# G021vrs.net
KiCad netlist of a schematic drawn in EAGLE
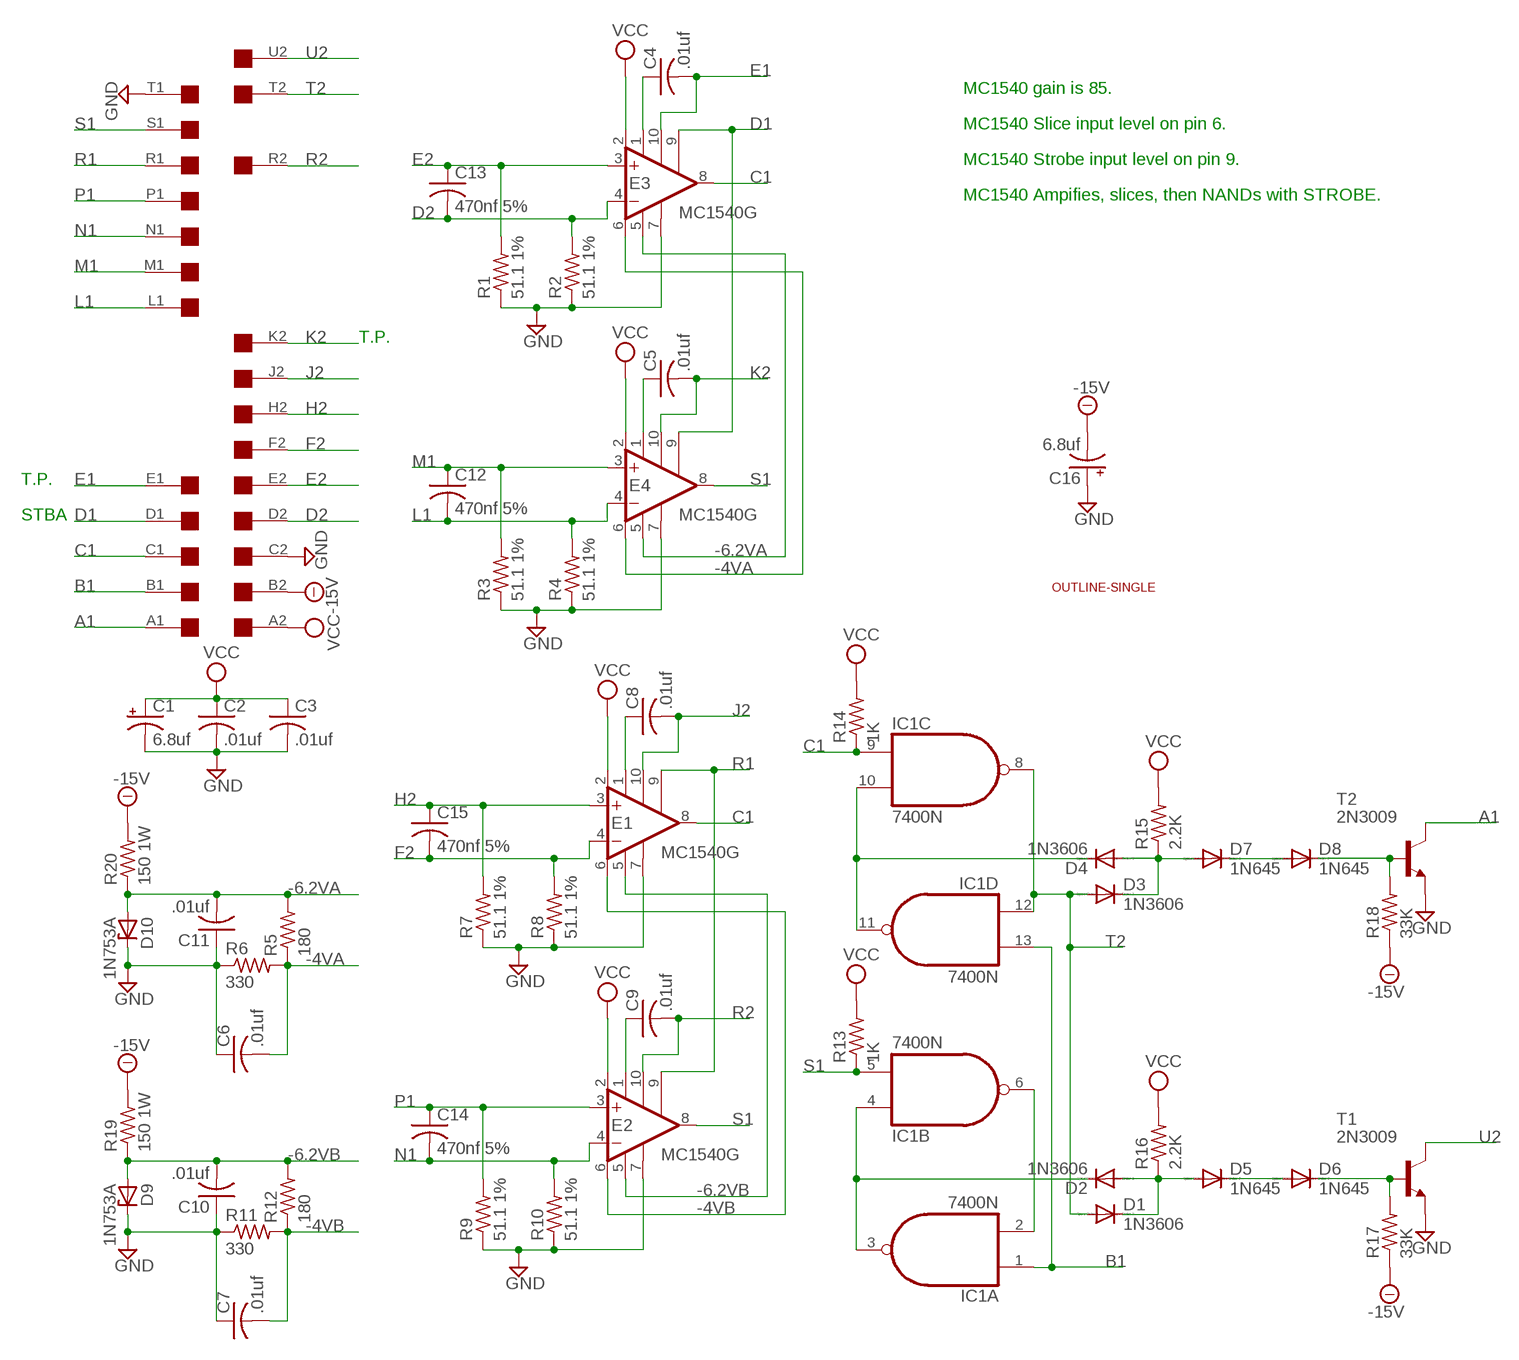
[diagram p0: schematic, sheet 1]

(export (version "E")
  (design (tool "Eeschema 10.0.6"))
  (components
    (comp (ref "C1")
      (value "6.8uf")
      (footprint "eagle-import:E15-5")
      (libsource (lib "eagle-import") (part "CPOL-USE15-5AXIAL"))
    )
    (comp (ref "C2")
      (value ".01uf")
      (footprint "eagle-import:C050-025X075")
      (libsource (lib "eagle-import") (part "C-US050-025X075"))
    )
    (comp (ref "C3")
      (value ".01uf")
      (footprint "eagle-import:C050-025X075")
      (libsource (lib "eagle-import") (part "C-US050-025X075"))
    )
    (comp (ref "C4")
      (value ".01uf")
      (footprint "eagle-import:C050-025X075")
      (libsource (lib "eagle-import") (part "C-US050-025X075"))
    )
    (comp (ref "C5")
      (value ".01uf")
      (footprint "eagle-import:C050-025X075")
      (libsource (lib "eagle-import") (part "C-US050-025X075"))
    )
    (comp (ref "C6")
      (value ".01uf")
      (footprint "eagle-import:C050-025X075")
      (libsource (lib "eagle-import") (part "C-US050-025X075"))
    )
    (comp (ref "C7")
      (value ".01uf")
      (footprint "eagle-import:C050-025X075")
      (libsource (lib "eagle-import") (part "C-US050-025X075"))
    )
    (comp (ref "C8")
      (value ".01uf")
      (footprint "eagle-import:C050-025X075")
      (libsource (lib "eagle-import") (part "C-US050-025X075"))
    )
    (comp (ref "C9")
      (value ".01uf")
      (footprint "eagle-import:C050-025X075")
      (libsource (lib "eagle-import") (part "C-US050-025X075"))
    )
    (comp (ref "C10")
      (value ".01uf")
      (footprint "eagle-import:C050-025X075")
      (libsource (lib "eagle-import") (part "C-US050-025X075"))
    )
    (comp (ref "C11")
      (value ".01uf")
      (footprint "eagle-import:C050-025X075")
      (libsource (lib "eagle-import") (part "C-US050-025X075"))
    )
    (comp (ref "C12")
      (value "470nf 5%")
      (footprint "eagle-import:C050-025X075")
      (libsource (lib "eagle-import") (part "C-US050-025X075"))
    )
    (comp (ref "C13")
      (value "470nf 5%")
      (footprint "eagle-import:C050-025X075")
      (libsource (lib "eagle-import") (part "C-US050-025X075"))
    )
    (comp (ref "C14")
      (value "470nf 5%")
      (footprint "eagle-import:C050-025X075")
      (libsource (lib "eagle-import") (part "C-US050-025X075"))
    )
    (comp (ref "C15")
      (value "470nf 5%")
      (footprint "eagle-import:C050-025X075")
      (libsource (lib "eagle-import") (part "C-US050-025X075"))
    )
    (comp (ref "C16")
      (value "6.8uf")
      (footprint "eagle-import:E15-5")
      (libsource (lib "eagle-import") (part "CPOL-USE15-5AXIAL"))
    )
    (comp (ref "D1")
      (value "1N3606")
      (footprint "eagle-import:DO35-10")
      (libsource (lib "eagle-import") (part "1N4148DO35-10"))
    )
    (comp (ref "D2")
      (value "1N3606")
      (footprint "eagle-import:DO35-10")
      (libsource (lib "eagle-import") (part "1N4148DO35-10"))
    )
    (comp (ref "D3")
      (value "1N3606")
      (footprint "eagle-import:DO35-10")
      (libsource (lib "eagle-import") (part "1N4148DO35-10"))
    )
    (comp (ref "D4")
      (value "1N3606")
      (footprint "eagle-import:DO35-10")
      (libsource (lib "eagle-import") (part "1N4148DO35-10"))
    )
    (comp (ref "D5")
      (value "1N645")
      (footprint "eagle-import:DO35-10")
      (libsource (lib "eagle-import") (part "1N4148DO35-10"))
    )
    (comp (ref "D6")
      (value "1N645")
      (footprint "eagle-import:DO35-10")
      (libsource (lib "eagle-import") (part "1N4148DO35-10"))
    )
    (comp (ref "D7")
      (value "1N645")
      (footprint "eagle-import:DO35-10")
      (libsource (lib "eagle-import") (part "1N4148DO35-10"))
    )
    (comp (ref "D8")
      (value "1N645")
      (footprint "eagle-import:DO35-10")
      (libsource (lib "eagle-import") (part "1N4148DO35-10"))
    )
    (comp (ref "D9")
      (value "1N753A")
      (footprint "eagle-import:F126Z10")
      (libsource (lib "eagle-import") (part "ZENER-DIODEF126-10"))
    )
    (comp (ref "D10")
      (value "1N753A")
      (footprint "eagle-import:F126Z10")
      (libsource (lib "eagle-import") (part "ZENER-DIODEF126-10"))
    )
    (comp (ref "E1")
      (value "MC1540G")
      (footprint "eagle-import:602B")
      (libsource (lib "eagle-import") (part "MC1540G"))
    )
    (comp (ref "E2")
      (value "MC1540G")
      (footprint "eagle-import:602B")
      (libsource (lib "eagle-import") (part "MC1540G"))
    )
    (comp (ref "E3")
      (value "MC1540G")
      (footprint "eagle-import:602B")
      (libsource (lib "eagle-import") (part "MC1540G"))
    )
    (comp (ref "E4")
      (value "MC1540G")
      (footprint "eagle-import:602B")
      (libsource (lib "eagle-import") (part "MC1540G"))
    )
    (comp (ref "IC1")
      (value "7400N")
      (footprint "eagle-import:DIL14")
      (libsource (lib "eagle-import") (part "7400N"))
    )
    (comp (ref "R1")
      (value "51.1 1%")
      (footprint "eagle-import:0207_10")
      (libsource (lib "eagle-import") (part "R-US_0207/10"))
    )
    (comp (ref "R2")
      (value "51.1 1%")
      (footprint "eagle-import:0207_10")
      (libsource (lib "eagle-import") (part "R-US_0207/10"))
    )
    (comp (ref "R3")
      (value "51.1 1%")
      (footprint "eagle-import:0207_10")
      (libsource (lib "eagle-import") (part "R-US_0207/10"))
    )
    (comp (ref "R4")
      (value "51.1 1%")
      (footprint "eagle-import:0207_10")
      (libsource (lib "eagle-import") (part "R-US_0207/10"))
    )
    (comp (ref "R5")
      (value "180")
      (footprint "eagle-import:0207_10")
      (libsource (lib "eagle-import") (part "R-US_0207/10"))
    )
    (comp (ref "R6")
      (value "330")
      (footprint "eagle-import:0207_10")
      (libsource (lib "eagle-import") (part "R-US_0207/10"))
    )
    (comp (ref "R7")
      (value "51.1 1%")
      (footprint "eagle-import:0207_10")
      (libsource (lib "eagle-import") (part "R-US_0207/10"))
    )
    (comp (ref "R8")
      (value "51.1 1%")
      (footprint "eagle-import:0207_10")
      (libsource (lib "eagle-import") (part "R-US_0207/10"))
    )
    (comp (ref "R9")
      (value "51.1 1%")
      (footprint "eagle-import:0207_10")
      (libsource (lib "eagle-import") (part "R-US_0207/10"))
    )
    (comp (ref "R10")
      (value "51.1 1%")
      (footprint "eagle-import:0207_10")
      (libsource (lib "eagle-import") (part "R-US_0207/10"))
    )
    (comp (ref "R11")
      (value "330")
      (footprint "eagle-import:0207_10")
      (libsource (lib "eagle-import") (part "R-US_0207/10"))
    )
    (comp (ref "R12")
      (value "180")
      (footprint "eagle-import:0207_10")
      (libsource (lib "eagle-import") (part "R-US_0207/10"))
    )
    (comp (ref "R13")
      (value "1K")
      (footprint "eagle-import:0207_10")
      (libsource (lib "eagle-import") (part "R-US_0207/10"))
    )
    (comp (ref "R14")
      (value "1K")
      (footprint "eagle-import:0207_10")
      (libsource (lib "eagle-import") (part "R-US_0207/10"))
    )
    (comp (ref "R15")
      (value "2.2K")
      (footprint "eagle-import:0207_10")
      (libsource (lib "eagle-import") (part "R-US_0207/10"))
    )
    (comp (ref "R16")
      (value "2.2K")
      (footprint "eagle-import:0207_10")
      (libsource (lib "eagle-import") (part "R-US_0207/10"))
    )
    (comp (ref "R17")
      (value "33K")
      (footprint "eagle-import:0207_10")
      (libsource (lib "eagle-import") (part "R-US_0207/10"))
    )
    (comp (ref "R18")
      (value "33K")
      (footprint "eagle-import:0207_10")
      (libsource (lib "eagle-import") (part "R-US_0207/10"))
    )
    (comp (ref "R19")
      (value "150 1W")
      (footprint "eagle-import:0414_15")
      (libsource (lib "eagle-import") (part "R-US_0414/15"))
    )
    (comp (ref "R20")
      (value "150 1W")
      (footprint "eagle-import:0414_15")
      (libsource (lib "eagle-import") (part "R-US_0414/15"))
    )
    (comp (ref "T1")
      (value "2N3009")
      (footprint "eagle-import:TO92")
      (libsource (lib "eagle-import") (part "2N3565"))
    )
    (comp (ref "T2")
      (value "2N3009")
      (footprint "eagle-import:TO92")
      (libsource (lib "eagle-import") (part "2N3565"))
    )
    (comp (ref "U$1")
      (value "SINGLE")
      (footprint "eagle-import:EDGE-CON2")
      (libsource (lib "eagle-import") (part "SINGLE"))
    )
    (comp (ref "U$2")
      (value "OUTLINE-SINGLE")
      (footprint "eagle-import:SINGLE")
      (libsource (lib "eagle-import") (part "OUTLINE-SINGLE"))
    )
  )
  (nets
    (net (code "1") (name "-15V") (class "Default")
      (node (ref "C16") (pin "-") (pinfunction "-_-") (pintype "passive"))
      (node (ref "R17") (pin "1") (pinfunction "1_1") (pintype "passive"))
      (node (ref "R18") (pin "1") (pinfunction "1_1") (pintype "passive"))
      (node (ref "R19") (pin "2") (pinfunction "2_2") (pintype "passive"))
      (node (ref "R20") (pin "2") (pinfunction "2_2") (pintype "passive"))
      (node (ref "U$1") (pin "B2") (pinfunction "1_B2") (pintype "bidirectional"))
    )
    (net (code "2") (name "/-4VA") (class "Default")
      (node (ref "C6") (pin "2") (pinfunction "2_2") (pintype "passive"))
      (node (ref "E3") (pin "6") (pinfunction "SLICE_6") (pintype "bidirectional"))
      (node (ref "E4") (pin "6") (pinfunction "SLICE_6") (pintype "bidirectional"))
      (node (ref "R5") (pin "1") (pinfunction "1_1") (pintype "passive"))
      (node (ref "R6") (pin "2") (pinfunction "2_2") (pintype "passive"))
    )
    (net (code "3") (name "/-4VB") (class "Default")
      (node (ref "C7") (pin "2") (pinfunction "2_2") (pintype "passive"))
      (node (ref "E1") (pin "6") (pinfunction "SLICE_6") (pintype "bidirectional"))
      (node (ref "E2") (pin "6") (pinfunction "SLICE_6") (pintype "bidirectional"))
      (node (ref "R11") (pin "2") (pinfunction "2_2") (pintype "passive"))
      (node (ref "R12") (pin "1") (pinfunction "1_1") (pintype "passive"))
    )
    (net (code "4") (name "/-6.2VA") (class "Default")
      (node (ref "C11") (pin "2") (pinfunction "2_2") (pintype "passive"))
      (node (ref "D10") (pin "A") (pinfunction "A_A") (pintype "passive"))
      (node (ref "E3") (pin "5") (pinfunction "V-_5") (pintype "power_in"))
      (node (ref "E4") (pin "5") (pinfunction "V-_5") (pintype "power_in"))
      (node (ref "R20") (pin "1") (pinfunction "1_1") (pintype "passive"))
      (node (ref "R5") (pin "2") (pinfunction "2_2") (pintype "passive"))
    )
    (net (code "5") (name "/-6.2VB") (class "Default")
      (node (ref "C10") (pin "2") (pinfunction "2_2") (pintype "passive"))
      (node (ref "D9") (pin "A") (pinfunction "A_A") (pintype "passive"))
      (node (ref "E1") (pin "5") (pinfunction "V-_5") (pintype "power_in"))
      (node (ref "E2") (pin "5") (pinfunction "V-_5") (pintype "power_in"))
      (node (ref "R12") (pin "2") (pinfunction "2_2") (pintype "passive"))
      (node (ref "R19") (pin "1") (pinfunction "1_1") (pintype "passive"))
    )
    (net (code "6") (name "/A1") (class "Default")
      (node (ref "T2") (pin "1") (pinfunction "C_1") (pintype "passive"))
      (node (ref "U$1") (pin "A1") (pinfunction "1_A1") (pintype "bidirectional"))
    )
    (net (code "7") (name "/B1") (class "Default")
      (node (ref "IC1") (pin "1") (pinfunction "I0_1") (pintype "input"))
      (node (ref "IC1") (pin "13") (pinfunction "I1_13") (pintype "input"))
      (node (ref "U$1") (pin "B1") (pinfunction "1_B1") (pintype "bidirectional"))
    )
    (net (code "8") (name "/C1") (class "Default")
      (node (ref "E1") (pin "8") (pinfunction "OUT_8") (pintype "open_collector"))
      (node (ref "E3") (pin "8") (pinfunction "OUT_8") (pintype "open_collector"))
      (node (ref "IC1") (pin "9") (pinfunction "I0_9") (pintype "input"))
      (node (ref "R14") (pin "1") (pinfunction "1_1") (pintype "passive"))
      (node (ref "U$1") (pin "C1") (pinfunction "1_C1") (pintype "bidirectional"))
    )
    (net (code "9") (name "/D1") (class "Default")
      (node (ref "E3") (pin "9") (pinfunction "ISTROBE_9") (pintype "passive"))
      (node (ref "E4") (pin "9") (pinfunction "ISTROBE_9") (pintype "passive"))
      (node (ref "U$1") (pin "D1") (pinfunction "1_D1") (pintype "bidirectional"))
    )
    (net (code "10") (name "/D2") (class "Default")
      (node (ref "C13") (pin "2") (pinfunction "2_2") (pintype "passive"))
      (node (ref "E3") (pin "4") (pinfunction "-IN_4") (pintype "input"))
      (node (ref "R2") (pin "2") (pinfunction "2_2") (pintype "passive"))
      (node (ref "U$1") (pin "D2") (pinfunction "1_D2") (pintype "bidirectional"))
    )
    (net (code "11") (name "/E1") (class "Default")
      (node (ref "C4") (pin "2") (pinfunction "2_2") (pintype "passive"))
      (node (ref "E3") (pin "10") (pinfunction "CEXTB_10") (pintype "passive"))
      (node (ref "U$1") (pin "E1") (pinfunction "1_E1") (pintype "bidirectional"))
    )
    (net (code "12") (name "/E2") (class "Default")
      (node (ref "C13") (pin "1") (pinfunction "1_1") (pintype "passive"))
      (node (ref "E3") (pin "3") (pinfunction "+IN_3") (pintype "input"))
      (node (ref "R1") (pin "2") (pinfunction "2_2") (pintype "passive"))
      (node (ref "U$1") (pin "E2") (pinfunction "1_E2") (pintype "bidirectional"))
    )
    (net (code "13") (name "/F2") (class "Default")
      (node (ref "C15") (pin "2") (pinfunction "2_2") (pintype "passive"))
      (node (ref "E1") (pin "4") (pinfunction "-IN_4") (pintype "input"))
      (node (ref "R8") (pin "2") (pinfunction "2_2") (pintype "passive"))
      (node (ref "U$1") (pin "F2") (pinfunction "1_F2") (pintype "bidirectional"))
    )
    (net (code "14") (name "/H2") (class "Default")
      (node (ref "C15") (pin "1") (pinfunction "1_1") (pintype "passive"))
      (node (ref "E1") (pin "3") (pinfunction "+IN_3") (pintype "input"))
      (node (ref "R7") (pin "2") (pinfunction "2_2") (pintype "passive"))
      (node (ref "U$1") (pin "H2") (pinfunction "1_H2") (pintype "bidirectional"))
    )
    (net (code "15") (name "/J2") (class "Default")
      (node (ref "C8") (pin "2") (pinfunction "2_2") (pintype "passive"))
      (node (ref "E1") (pin "10") (pinfunction "CEXTB_10") (pintype "passive"))
      (node (ref "U$1") (pin "J2") (pinfunction "1_J2") (pintype "bidirectional"))
    )
    (net (code "16") (name "/K2") (class "Default")
      (node (ref "C5") (pin "2") (pinfunction "2_2") (pintype "passive"))
      (node (ref "E4") (pin "10") (pinfunction "CEXTB_10") (pintype "passive"))
      (node (ref "U$1") (pin "K2") (pinfunction "1_K2") (pintype "bidirectional"))
    )
    (net (code "17") (name "/L1") (class "Default")
      (node (ref "C12") (pin "2") (pinfunction "2_2") (pintype "passive"))
      (node (ref "E4") (pin "4") (pinfunction "-IN_4") (pintype "input"))
      (node (ref "R4") (pin "2") (pinfunction "2_2") (pintype "passive"))
      (node (ref "U$1") (pin "L1") (pinfunction "1_L1") (pintype "bidirectional"))
    )
    (net (code "18") (name "/M1") (class "Default")
      (node (ref "C12") (pin "1") (pinfunction "1_1") (pintype "passive"))
      (node (ref "E4") (pin "3") (pinfunction "+IN_3") (pintype "input"))
      (node (ref "R3") (pin "2") (pinfunction "2_2") (pintype "passive"))
      (node (ref "U$1") (pin "M1") (pinfunction "1_M1") (pintype "bidirectional"))
    )
    (net (code "19") (name "/N1") (class "Default")
      (node (ref "C14") (pin "2") (pinfunction "2_2") (pintype "passive"))
      (node (ref "E2") (pin "4") (pinfunction "-IN_4") (pintype "input"))
      (node (ref "R10") (pin "2") (pinfunction "2_2") (pintype "passive"))
      (node (ref "U$1") (pin "N1") (pinfunction "1_N1") (pintype "bidirectional"))
    )
    (net (code "20") (name "/P1") (class "Default")
      (node (ref "C14") (pin "1") (pinfunction "1_1") (pintype "passive"))
      (node (ref "E2") (pin "3") (pinfunction "+IN_3") (pintype "input"))
      (node (ref "R9") (pin "2") (pinfunction "2_2") (pintype "passive"))
      (node (ref "U$1") (pin "P1") (pinfunction "1_P1") (pintype "bidirectional"))
    )
    (net (code "21") (name "/R1") (class "Default")
      (node (ref "E1") (pin "9") (pinfunction "ISTROBE_9") (pintype "passive"))
      (node (ref "E2") (pin "9") (pinfunction "ISTROBE_9") (pintype "passive"))
      (node (ref "U$1") (pin "R1") (pinfunction "1_R1") (pintype "bidirectional"))
    )
    (net (code "22") (name "/R2") (class "Default")
      (node (ref "C9") (pin "2") (pinfunction "2_2") (pintype "passive"))
      (node (ref "E2") (pin "10") (pinfunction "CEXTB_10") (pintype "passive"))
      (node (ref "U$1") (pin "R2") (pinfunction "1_R2") (pintype "bidirectional"))
    )
    (net (code "23") (name "/S1") (class "Default")
      (node (ref "E2") (pin "8") (pinfunction "OUT_8") (pintype "open_collector"))
      (node (ref "E4") (pin "8") (pinfunction "OUT_8") (pintype "open_collector"))
      (node (ref "IC1") (pin "5") (pinfunction "I1_5") (pintype "input"))
      (node (ref "R13") (pin "1") (pinfunction "1_1") (pintype "passive"))
      (node (ref "U$1") (pin "S1") (pinfunction "1_S1") (pintype "bidirectional"))
    )
    (net (code "24") (name "/T2") (class "Default")
      (node (ref "D1") (pin "A") (pinfunction "A_A") (pintype "passive"))
      (node (ref "D3") (pin "A") (pinfunction "A_A") (pintype "passive"))
      (node (ref "IC1") (pin "12") (pinfunction "I0_12") (pintype "input"))
      (node (ref "IC1") (pin "8") (pinfunction "O_8") (pintype "output"))
      (node (ref "U$1") (pin "T2") (pinfunction "1_T2") (pintype "bidirectional"))
    )
    (net (code "25") (name "/U2") (class "Default")
      (node (ref "T1") (pin "1") (pinfunction "C_1") (pintype "passive"))
      (node (ref "U$1") (pin "U2") (pinfunction "1_U2") (pintype "bidirectional"))
    )
    (net (code "26") (name "GND") (class "Default")
      (node (ref "C1") (pin "-") (pinfunction "-_-") (pintype "passive"))
      (node (ref "C10") (pin "1") (pinfunction "1_1") (pintype "passive"))
      (node (ref "C11") (pin "1") (pinfunction "1_1") (pintype "passive"))
      (node (ref "C16") (pin "+") (pinfunction "+_+") (pintype "passive"))
      (node (ref "C2") (pin "2") (pinfunction "2_2") (pintype "passive"))
      (node (ref "C3") (pin "2") (pinfunction "2_2") (pintype "passive"))
      (node (ref "C6") (pin "1") (pinfunction "1_1") (pintype "passive"))
      (node (ref "C7") (pin "1") (pinfunction "1_1") (pintype "passive"))
      (node (ref "D10") (pin "C") (pinfunction "C_C") (pintype "passive"))
      (node (ref "D9") (pin "C") (pinfunction "C_C") (pintype "passive"))
      (node (ref "E1") (pin "7") (pinfunction "GND_7") (pintype "power_in"))
      (node (ref "E2") (pin "7") (pinfunction "GND_7") (pintype "power_in"))
      (node (ref "E3") (pin "7") (pinfunction "GND_7") (pintype "power_in"))
      (node (ref "E4") (pin "7") (pinfunction "GND_7") (pintype "power_in"))
      (node (ref "R1") (pin "1") (pinfunction "1_1") (pintype "passive"))
      (node (ref "R10") (pin "1") (pinfunction "1_1") (pintype "passive"))
      (node (ref "R11") (pin "1") (pinfunction "1_1") (pintype "passive"))
      (node (ref "R2") (pin "1") (pinfunction "1_1") (pintype "passive"))
      (node (ref "R3") (pin "1") (pinfunction "1_1") (pintype "passive"))
      (node (ref "R4") (pin "1") (pinfunction "1_1") (pintype "passive"))
      (node (ref "R6") (pin "1") (pinfunction "1_1") (pintype "passive"))
      (node (ref "R7") (pin "1") (pinfunction "1_1") (pintype "passive"))
      (node (ref "R8") (pin "1") (pinfunction "1_1") (pintype "passive"))
      (node (ref "R9") (pin "1") (pinfunction "1_1") (pintype "passive"))
      (node (ref "T1") (pin "3") (pinfunction "E_3") (pintype "passive"))
      (node (ref "T2") (pin "3") (pinfunction "E_3") (pintype "passive"))
      (node (ref "U$1") (pin "C2") (pinfunction "1_C2") (pintype "bidirectional"))
      (node (ref "U$1") (pin "T1") (pinfunction "1_T1") (pintype "bidirectional"))
    )
    (net (code "27") (name "Net-(D1-PadC)") (class "Default")
      (node (ref "D1") (pin "C") (pinfunction "C_C") (pintype "passive"))
      (node (ref "D2") (pin "A") (pinfunction "A_A") (pintype "passive"))
      (node (ref "D5") (pin "A") (pinfunction "A_A") (pintype "passive"))
      (node (ref "R16") (pin "1") (pinfunction "1_1") (pintype "passive"))
    )
    (net (code "28") (name "Net-(D3-PadC)") (class "Default")
      (node (ref "D3") (pin "C") (pinfunction "C_C") (pintype "passive"))
      (node (ref "D4") (pin "A") (pinfunction "A_A") (pintype "passive"))
      (node (ref "D7") (pin "A") (pinfunction "A_A") (pintype "passive"))
      (node (ref "R15") (pin "1") (pinfunction "1_1") (pintype "passive"))
    )
    (net (code "29") (name "Net-(D5-PadC)") (class "Default")
      (node (ref "D5") (pin "C") (pinfunction "C_C") (pintype "passive"))
      (node (ref "D6") (pin "A") (pinfunction "A_A") (pintype "passive"))
    )
    (net (code "30") (name "Net-(D7-PadC)") (class "Default")
      (node (ref "D7") (pin "C") (pinfunction "C_C") (pintype "passive"))
      (node (ref "D8") (pin "A") (pinfunction "A_A") (pintype "passive"))
    )
    (net (code "31") (name "Net-(E1-CEXTA)") (class "Default")
      (node (ref "C8") (pin "1") (pinfunction "1_1") (pintype "passive"))
      (node (ref "E1") (pin "1") (pinfunction "CEXTA_1") (pintype "passive"))
    )
    (net (code "32") (name "Net-(E2-CEXTA)") (class "Default")
      (node (ref "C9") (pin "1") (pinfunction "1_1") (pintype "passive"))
      (node (ref "E2") (pin "1") (pinfunction "CEXTA_1") (pintype "passive"))
    )
    (net (code "33") (name "Net-(E3-CEXTA)") (class "Default")
      (node (ref "C4") (pin "1") (pinfunction "1_1") (pintype "passive"))
      (node (ref "E3") (pin "1") (pinfunction "CEXTA_1") (pintype "passive"))
    )
    (net (code "34") (name "Net-(E4-CEXTA)") (class "Default")
      (node (ref "C5") (pin "1") (pinfunction "1_1") (pintype "passive"))
      (node (ref "E4") (pin "1") (pinfunction "CEXTA_1") (pintype "passive"))
    )
    (net (code "35") (name "Net-(IC1A-I1)") (class "Default")
      (node (ref "IC1") (pin "2") (pinfunction "I1_2") (pintype "input"))
      (node (ref "IC1") (pin "6") (pinfunction "O_6") (pintype "output"))
    )
    (net (code "36") (name "Net-(IC1A-O)") (class "Default")
      (node (ref "D2") (pin "C") (pinfunction "C_C") (pintype "passive"))
      (node (ref "IC1") (pin "3") (pinfunction "O_3") (pintype "output"))
      (node (ref "IC1") (pin "4") (pinfunction "I0_4") (pintype "input"))
    )
    (net (code "37") (name "Net-(IC1C-I1)") (class "Default")
      (node (ref "D4") (pin "C") (pinfunction "C_C") (pintype "passive"))
      (node (ref "IC1") (pin "10") (pinfunction "I1_10") (pintype "input"))
      (node (ref "IC1") (pin "11") (pinfunction "O_11") (pintype "output"))
    )
    (net (code "38") (name "Net-(T1-B)") (class "Default")
      (node (ref "D6") (pin "C") (pinfunction "C_C") (pintype "passive"))
      (node (ref "R17") (pin "2") (pinfunction "2_2") (pintype "passive"))
      (node (ref "T1") (pin "2") (pinfunction "B_2") (pintype "passive"))
    )
    (net (code "39") (name "Net-(T2-B)") (class "Default")
      (node (ref "D8") (pin "C") (pinfunction "C_C") (pintype "passive"))
      (node (ref "R18") (pin "2") (pinfunction "2_2") (pintype "passive"))
      (node (ref "T2") (pin "2") (pinfunction "B_2") (pintype "passive"))
    )
    (net (code "40") (name "VCC") (class "Default")
      (node (ref "C1") (pin "+") (pinfunction "+_+") (pintype "passive"))
      (node (ref "C2") (pin "1") (pinfunction "1_1") (pintype "passive"))
      (node (ref "C3") (pin "1") (pinfunction "1_1") (pintype "passive"))
      (node (ref "E1") (pin "2") (pinfunction "V+_2") (pintype "power_in"))
      (node (ref "E2") (pin "2") (pinfunction "V+_2") (pintype "power_in"))
      (node (ref "E3") (pin "2") (pinfunction "V+_2") (pintype "power_in"))
      (node (ref "E4") (pin "2") (pinfunction "V+_2") (pintype "power_in"))
      (node (ref "R13") (pin "2") (pinfunction "2_2") (pintype "passive"))
      (node (ref "R14") (pin "2") (pinfunction "2_2") (pintype "passive"))
      (node (ref "R15") (pin "2") (pinfunction "2_2") (pintype "passive"))
      (node (ref "R16") (pin "2") (pinfunction "2_2") (pintype "passive"))
      (node (ref "U$1") (pin "A2") (pinfunction "1_A2") (pintype "bidirectional"))
    )
  )
)
